# Riego_2_0.net
KiCad netlist of a schematic drawn in EasyEDA
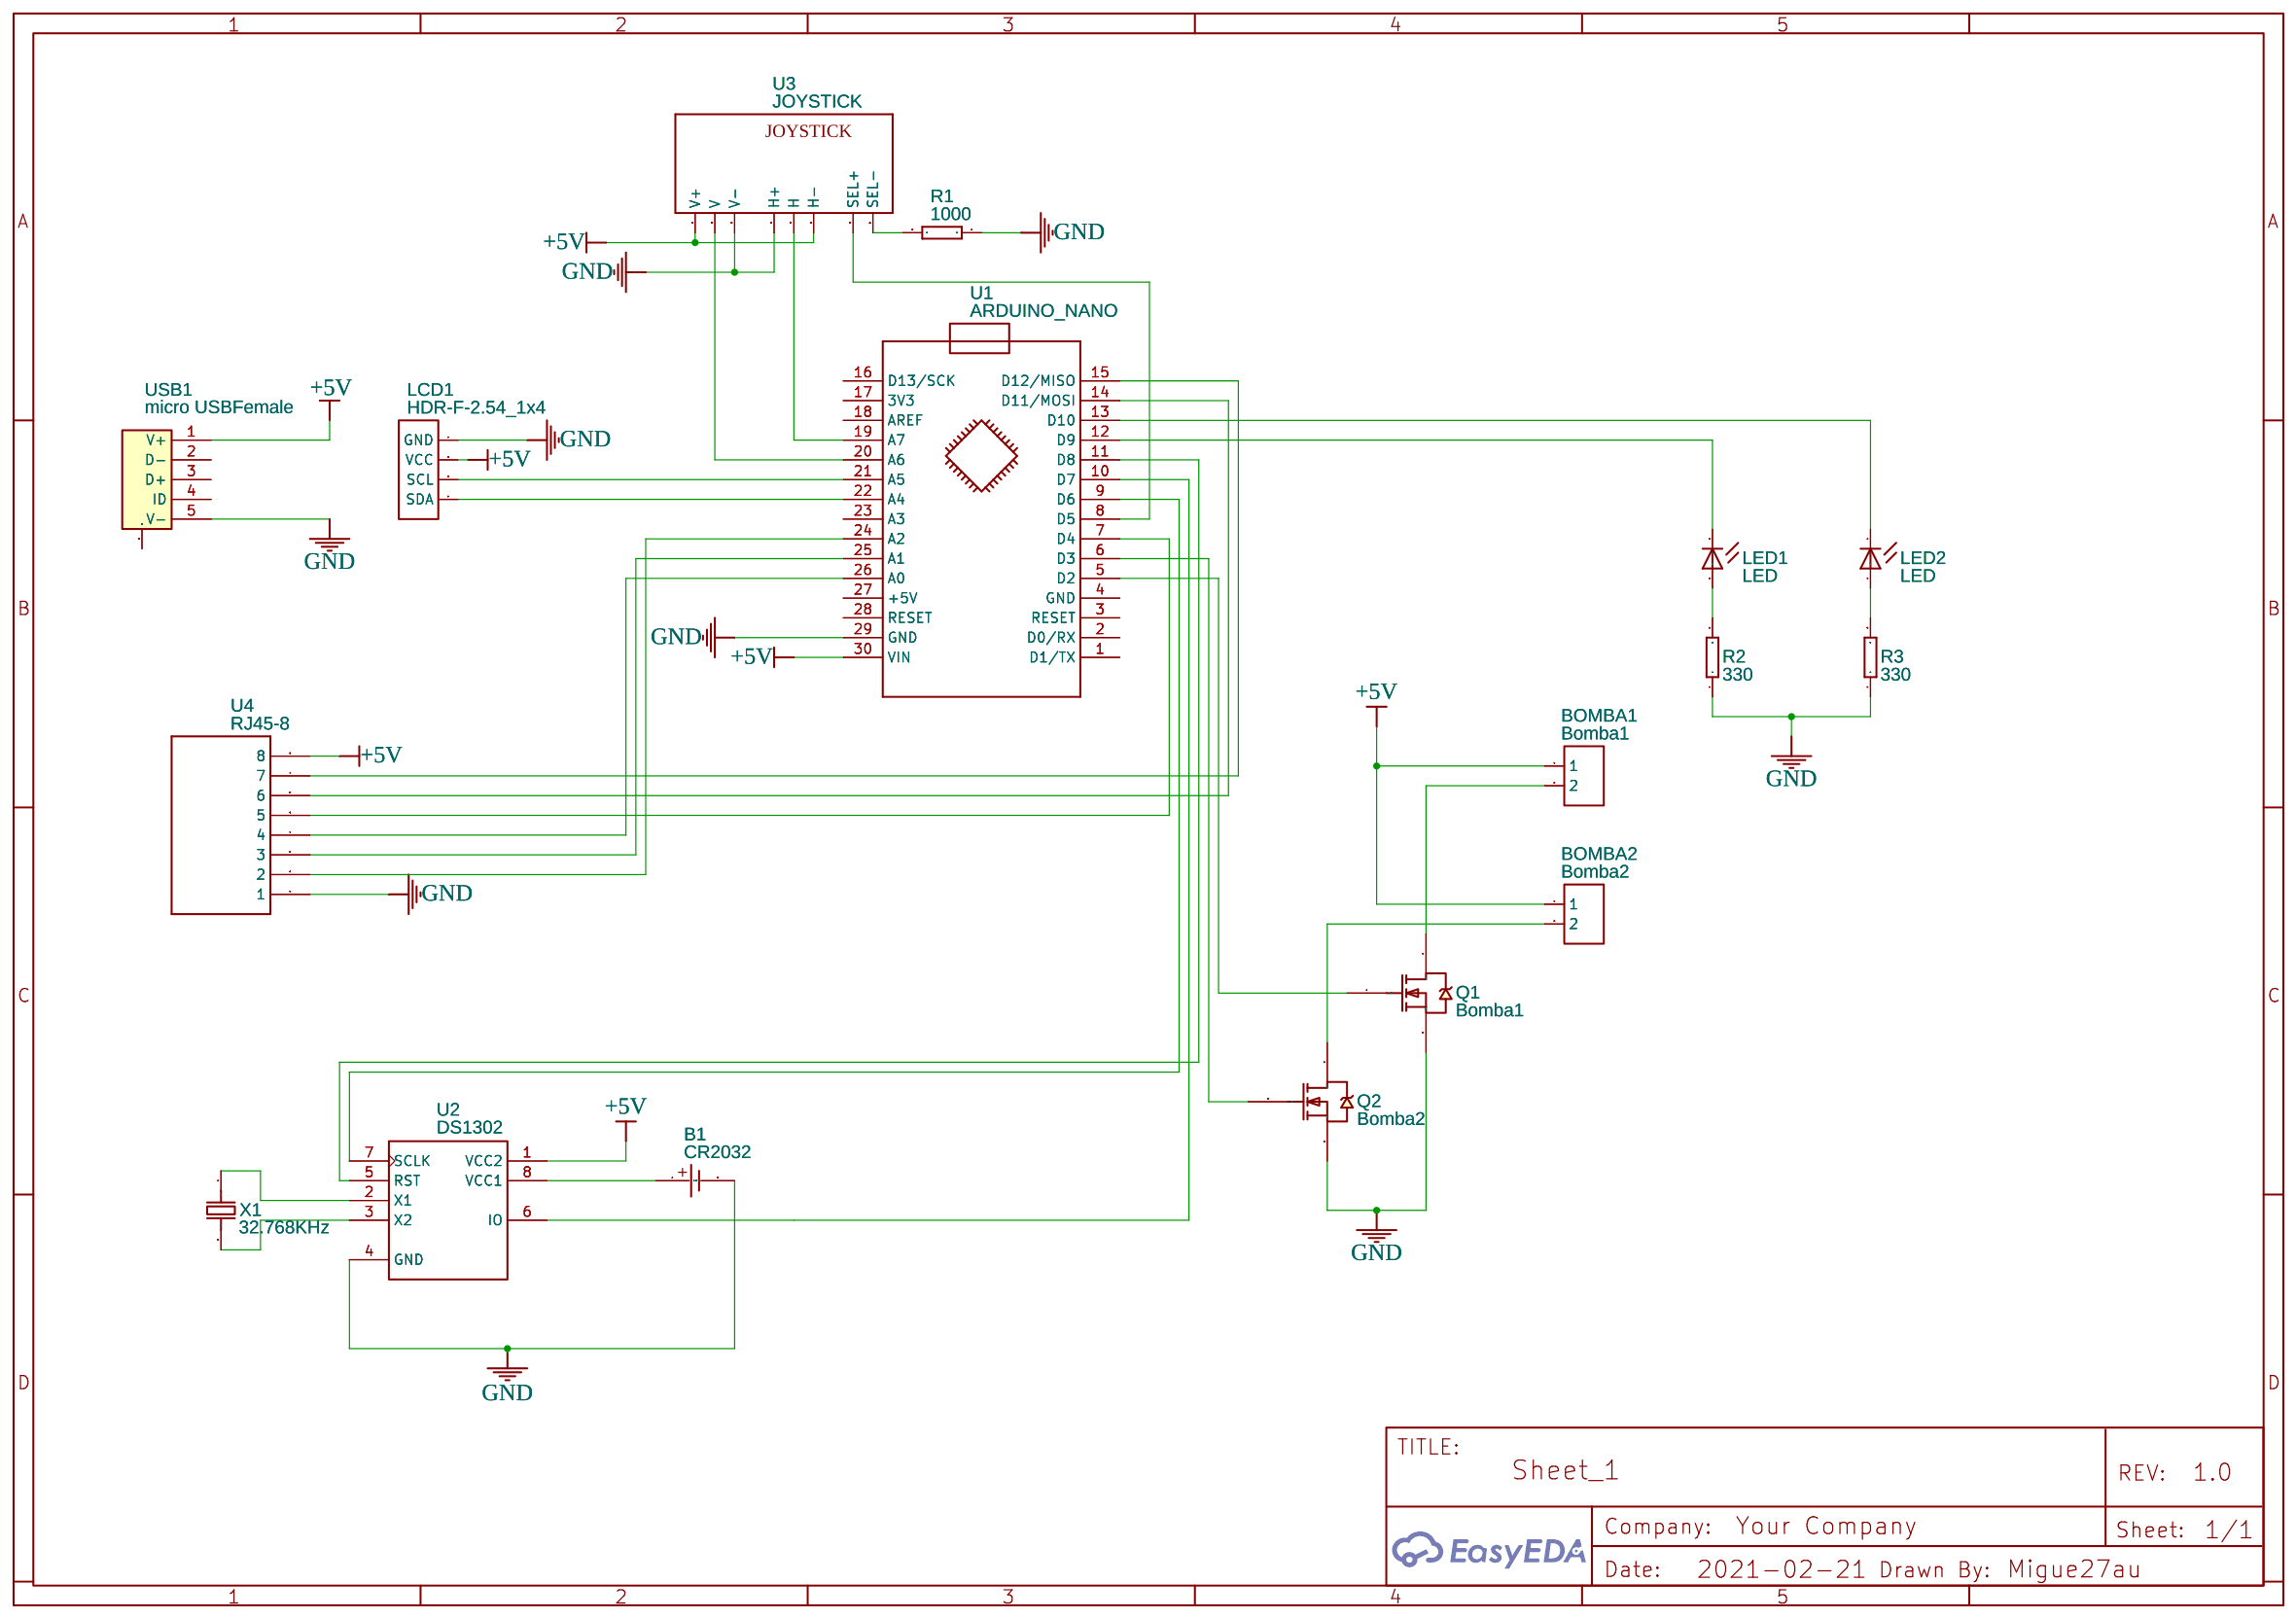
[diagram p0: schematic sheet]

(export (version "E")
  (design (tool "Eeschema 10.0.6"))
  (components
    (comp (ref "B1")
      (value "CR2032")
      (fields (field (name "BOM_Manufacturer Part") "BS-2-1") (field (name "BOM_Supplier Part") "C70376"))
      (libsource (lib "") (part "CR2032"))
    )
    (comp (ref "BOMBA1") (value "Bomba1") (libsource (lib "") (part "CONN-TH_2P-P5.08")))
    (comp (ref "BOMBA2") (value "Bomba2") (libsource (lib "") (part "CONN-TH_2P-P5.08")))
    (comp (ref "LCD1")
      (value "HDR-F-2.54_1x4")
      (fields (field (name "BOM_Supplier Part") "C225501"))
      (libsource (lib "") (part "HDR-F-2.54_1x4"))
    )
    (comp (ref "LED1") (value "LED") (libsource (lib "") (part "LED")))
    (comp (ref "LED2") (value "LED") (libsource (lib "") (part "LED")))
    (comp (ref "Q1") (value "Bomba1") (libsource (lib "") (part "IRF740")))
    (comp (ref "Q2") (value "Bomba2") (libsource (lib "") (part "IRF740")))
    (comp (ref "R1") (value "1000") (libsource (lib "") (part "RESISTOR")))
    (comp (ref "R2") (value "330") (libsource (lib "") (part "RESISTOR_1")))
    (comp (ref "R3") (value "330") (libsource (lib "") (part "RESISTOR_1")))
    (comp (ref "U1") (value "ARDUINO_NANO") (libsource (lib "") (part "ARDUINO_NANO")))
    (comp (ref "U2") (value "DS1302") (libsource (lib "") (part "DS1302")))
    (comp (ref "U3") (value "JOYSTICK") (libsource (lib "") (part "JOYSTICK")))
    (comp (ref "U4") (value "RJ45-8") (libsource (lib "") (part "RJ45-8")))
    (comp (ref "USB1")
      (value "micro USBFemale")
      (fields (field (name "BOM_Supplier Part") "C10418"))
      (libsource (lib "") (part "micro USBFemale"))
    )
    (comp (ref "X1")
      (value "32.768KHz")
      (fields
        (field (name "BOM_Manufacturer Part") "DT-38 32.768KHz")
        (field (name "BOM_Supplier Part") "C93228")
      )
      (libsource (lib "") (part "DT-38 32.768KHZ COPY"))
    )
  )
  (nets
    (net (code "1") (name "+5V") (class "Default")
      (node (ref "BOMBA1") (pin "1") (pinfunction "1_1") (pintype "unspecified"))
      (node (ref "BOMBA2") (pin "1") (pinfunction "1_1") (pintype "unspecified"))
      (node (ref "LCD1") (pin "3") (pinfunction "VCC_3") (pintype "unspecified"))
      (node (ref "U1") (pin "30") (pinfunction "VIN_30") (pintype "unspecified"))
      (node (ref "U2") (pin "1") (pinfunction "VCC2_1") (pintype "passive"))
      (node (ref "U3") (pin "H3") (pinfunction "H-_H3") (pintype "unspecified"))
      (node (ref "U3") (pin "V1") (pinfunction "V+_V1") (pintype "unspecified"))
      (node (ref "U4") (pin "8") (pinfunction "8_8") (pintype "unspecified"))
      (node (ref "USB1") (pin "1") (pinfunction "V+_1") (pintype "unspecified"))
    )
    (net (code "2") (name "GND") (class "Default")
      (node (ref "B1") (pin "2") (pinfunction "2_2") (pintype "input"))
      (node (ref "LCD1") (pin "4") (pinfunction "GND_4") (pintype "unspecified"))
      (node (ref "Q1") (pin "3") (pinfunction "S_3") (pintype "unspecified"))
      (node (ref "Q2") (pin "3") (pinfunction "S_3") (pintype "unspecified"))
      (node (ref "R1") (pin "1") (pinfunction "1_1") (pintype "unspecified"))
      (node (ref "R2") (pin "1") (pinfunction "1_1") (pintype "unspecified"))
      (node (ref "R3") (pin "1") (pinfunction "1_1") (pintype "unspecified"))
      (node (ref "U1") (pin "29") (pinfunction "GND_29") (pintype "unspecified"))
      (node (ref "U2") (pin "4") (pinfunction "GND_4") (pintype "passive"))
      (node (ref "U3") (pin "H1") (pinfunction "H+_H1") (pintype "unspecified"))
      (node (ref "U3") (pin "V3") (pinfunction "V-_V3") (pintype "unspecified"))
      (node (ref "U4") (pin "1") (pinfunction "1_1") (pintype "unspecified"))
      (node (ref "USB1") (pin "5") (pinfunction "V-_5") (pintype "unspecified"))
    )
    (net (code "3") (name "Net-(LCD1-SCL)") (class "Default")
      (node (ref "LCD1") (pin "2") (pinfunction "SCL_2") (pintype "unspecified"))
      (node (ref "U1") (pin "21") (pinfunction "A5_21") (pintype "unspecified"))
    )
    (net (code "4") (name "Net-(LCD1-SDA)") (class "Default")
      (node (ref "LCD1") (pin "1") (pinfunction "SDA_1") (pintype "unspecified"))
      (node (ref "U1") (pin "22") (pinfunction "A4_22") (pintype "unspecified"))
    )
    (net (code "5") (name "Net-(LED1-C)") (class "Default")
      (node (ref "LED1") (pin "K") (pinfunction "C_K") (pintype "unspecified"))
      (node (ref "U1") (pin "12") (pinfunction "D9_12") (pintype "unspecified"))
    )
    (net (code "6") (name "Net-(LED1-PadA)") (class "Default")
      (node (ref "LED1") (pin "A") (pinfunction "A_A") (pintype "unspecified"))
      (node (ref "R2") (pin "2") (pinfunction "2_2") (pintype "unspecified"))
    )
    (net (code "7") (name "Net-(LED2-C)") (class "Default")
      (node (ref "LED2") (pin "K") (pinfunction "C_K") (pintype "unspecified"))
      (node (ref "U1") (pin "13") (pinfunction "D10_13") (pintype "unspecified"))
    )
    (net (code "8") (name "Net-(LED2-PadA)") (class "Default")
      (node (ref "LED2") (pin "A") (pinfunction "A_A") (pintype "unspecified"))
      (node (ref "R3") (pin "2") (pinfunction "2_2") (pintype "unspecified"))
    )
    (net (code "9") (name "Net-(Q1-D)") (class "Default")
      (node (ref "BOMBA1") (pin "2") (pinfunction "2_2") (pintype "unspecified"))
      (node (ref "Q1") (pin "2") (pinfunction "D_2") (pintype "unspecified"))
    )
    (net (code "10") (name "Net-(Q1-G)") (class "Default")
      (node (ref "Q1") (pin "1") (pinfunction "G_1") (pintype "unspecified"))
      (node (ref "U1") (pin "5") (pinfunction "D2_5") (pintype "unspecified"))
    )
    (net (code "11") (name "Net-(Q2-D)") (class "Default")
      (node (ref "BOMBA2") (pin "2") (pinfunction "2_2") (pintype "unspecified"))
      (node (ref "Q2") (pin "2") (pinfunction "D_2") (pintype "unspecified"))
    )
    (net (code "12") (name "Net-(Q2-G)") (class "Default")
      (node (ref "Q2") (pin "1") (pinfunction "G_1") (pintype "unspecified"))
      (node (ref "U1") (pin "6") (pinfunction "D3_6") (pintype "unspecified"))
    )
    (net (code "13") (name "Net-(U1-A0)") (class "Default")
      (node (ref "U1") (pin "26") (pinfunction "A0_26") (pintype "unspecified"))
      (node (ref "U4") (pin "4") (pinfunction "4_4") (pintype "unspecified"))
    )
    (net (code "14") (name "Net-(U1-A1)") (class "Default")
      (node (ref "U1") (pin "25") (pinfunction "A1_25") (pintype "unspecified"))
      (node (ref "U4") (pin "3") (pinfunction "3_3") (pintype "unspecified"))
    )
    (net (code "15") (name "Net-(U1-A2)") (class "Default")
      (node (ref "U1") (pin "24") (pinfunction "A2_24") (pintype "unspecified"))
      (node (ref "U4") (pin "2") (pinfunction "2_2") (pintype "unspecified"))
    )
    (net (code "16") (name "Net-(U1-A6)") (class "Default")
      (node (ref "U1") (pin "20") (pinfunction "A6_20") (pintype "unspecified"))
      (node (ref "U3") (pin "V2") (pinfunction "V_V2") (pintype "unspecified"))
    )
    (net (code "17") (name "Net-(U1-A7)") (class "Default")
      (node (ref "U1") (pin "19") (pinfunction "A7_19") (pintype "unspecified"))
      (node (ref "U3") (pin "H2") (pinfunction "H_H2") (pintype "unspecified"))
    )
    (net (code "18") (name "Net-(U1-D4)") (class "Default")
      (node (ref "U1") (pin "7") (pinfunction "D4_7") (pintype "unspecified"))
      (node (ref "U4") (pin "5") (pinfunction "5_5") (pintype "unspecified"))
    )
    (net (code "19") (name "Net-(U1-D5)") (class "Default")
      (node (ref "U1") (pin "8") (pinfunction "D5_8") (pintype "unspecified"))
      (node (ref "U3") (pin "B1A") (pinfunction "SEL+_B1A") (pintype "unspecified"))
    )
    (net (code "20") (name "Net-(U1-D6)") (class "Default")
      (node (ref "U1") (pin "9") (pinfunction "D6_9") (pintype "unspecified"))
      (node (ref "U2") (pin "7") (pinfunction "SCLK_7") (pintype "unspecified"))
    )
    (net (code "21") (name "Net-(U1-D7)") (class "Default")
      (node (ref "U1") (pin "10") (pinfunction "D7_10") (pintype "unspecified"))
      (node (ref "U2") (pin "6") (pinfunction "IO_6") (pintype "bidirectional"))
    )
    (net (code "22") (name "Net-(U1-D8)") (class "Default")
      (node (ref "U1") (pin "11") (pinfunction "D8_11") (pintype "unspecified"))
      (node (ref "U2") (pin "5") (pinfunction "RST_5") (pintype "unspecified"))
    )
    (net (code "23") (name "Net-(U1-D11{slash}MOSI)") (class "Default")
      (node (ref "U1") (pin "14") (pinfunction "D11/MOSI_14") (pintype "unspecified"))
      (node (ref "U4") (pin "6") (pinfunction "6_6") (pintype "unspecified"))
    )
    (net (code "24") (name "Net-(U1-D12{slash}MISO)") (class "Default")
      (node (ref "U1") (pin "15") (pinfunction "D12/MISO_15") (pintype "unspecified"))
      (node (ref "U4") (pin "7") (pinfunction "7_7") (pintype "unspecified"))
    )
    (net (code "25") (name "Net-(U2-VCC1)") (class "Default")
      (node (ref "B1") (pin "1") (pinfunction "1_1") (pintype "input"))
      (node (ref "U2") (pin "8") (pinfunction "VCC1_8") (pintype "passive"))
    )
    (net (code "26") (name "Net-(U2-X1)") (class "Default")
      (node (ref "U2") (pin "2") (pinfunction "X1_2") (pintype "unspecified"))
      (node (ref "X1") (pin "1") (pinfunction "1_1") (pintype "unspecified"))
    )
    (net (code "27") (name "Net-(U2-X2)") (class "Default")
      (node (ref "U2") (pin "3") (pinfunction "X2_3") (pintype "unspecified"))
      (node (ref "X1") (pin "2") (pinfunction "2_2") (pintype "unspecified"))
    )
    (net (code "28") (name "Net-(U3-SEL-)") (class "Default")
      (node (ref "R1") (pin "2") (pinfunction "2_2") (pintype "unspecified"))
      (node (ref "U3") (pin "B2A") (pinfunction "SEL-_B2A") (pintype "unspecified"))
    )
    (net (code "29") (name "unconnected-(U1-+5V-Pad27)") (class "Default")
      (node (ref "U1") (pin "27") (pinfunction "+5V_27") (pintype "unspecified"))
    )
    (net (code "30") (name "unconnected-(U1-3V3-Pad17)") (class "Default")
      (node (ref "U1") (pin "17") (pinfunction "3V3_17") (pintype "unspecified"))
    )
    (net (code "31") (name "unconnected-(U1-A3-Pad23)") (class "Default")
      (node (ref "U1") (pin "23") (pinfunction "A3_23") (pintype "unspecified"))
    )
    (net (code "32") (name "unconnected-(U1-AREF-Pad18)") (class "Default")
      (node (ref "U1") (pin "18") (pinfunction "AREF_18") (pintype "unspecified"))
    )
    (net (code "33") (name "unconnected-(U1-D0{slash}RX-Pad2)") (class "Default")
      (node (ref "U1") (pin "2") (pinfunction "D0/RX_2") (pintype "unspecified"))
    )
    (net (code "34") (name "unconnected-(U1-D1{slash}TX-Pad1)") (class "Default")
      (node (ref "U1") (pin "1") (pinfunction "D1/TX_1") (pintype "unspecified"))
    )
    (net (code "35") (name "unconnected-(U1-D13{slash}SCK-Pad16)") (class "Default")
      (node (ref "U1") (pin "16") (pinfunction "D13/SCK_16") (pintype "unspecified"))
    )
    (net (code "36") (name "unconnected-(U1-GND-Pad4)") (class "Default")
      (node (ref "U1") (pin "4") (pinfunction "GND_4") (pintype "unspecified"))
    )
    (net (code "37") (name "unconnected-(U1-RESET-Pad3)") (class "Default")
      (node (ref "U1") (pin "3") (pinfunction "RESET_3") (pintype "unspecified"))
    )
    (net (code "38") (name "unconnected-(U1-RESET-Pad28)") (class "Default")
      (node (ref "U1") (pin "28") (pinfunction "RESET_28") (pintype "unspecified"))
    )
    (net (code "39") (name "unconnected-(USB1-D+-Pad3)") (class "Default")
      (node (ref "USB1") (pin "3") (pinfunction "D+_3") (pintype "unspecified"))
    )
    (net (code "40") (name "unconnected-(USB1-D--Pad2)") (class "Default")
      (node (ref "USB1") (pin "2") (pinfunction "D-_2") (pintype "unspecified"))
    )
    (net (code "41") (name "unconnected-(USB1-ID-Pad4)") (class "Default")
      (node (ref "USB1") (pin "4") (pinfunction "ID_4") (pintype "unspecified"))
    )
    (net (code "42") (name "unconnected-(USB1-MTN-Pad0)") (class "Default")
      (node (ref "USB1") (pin "0") (pinfunction "MTN_0") (pintype "input"))
    )
  )
)
